# FPGA_PLLs.net
KiCad netlist of a schematic drawn in Altium Designer
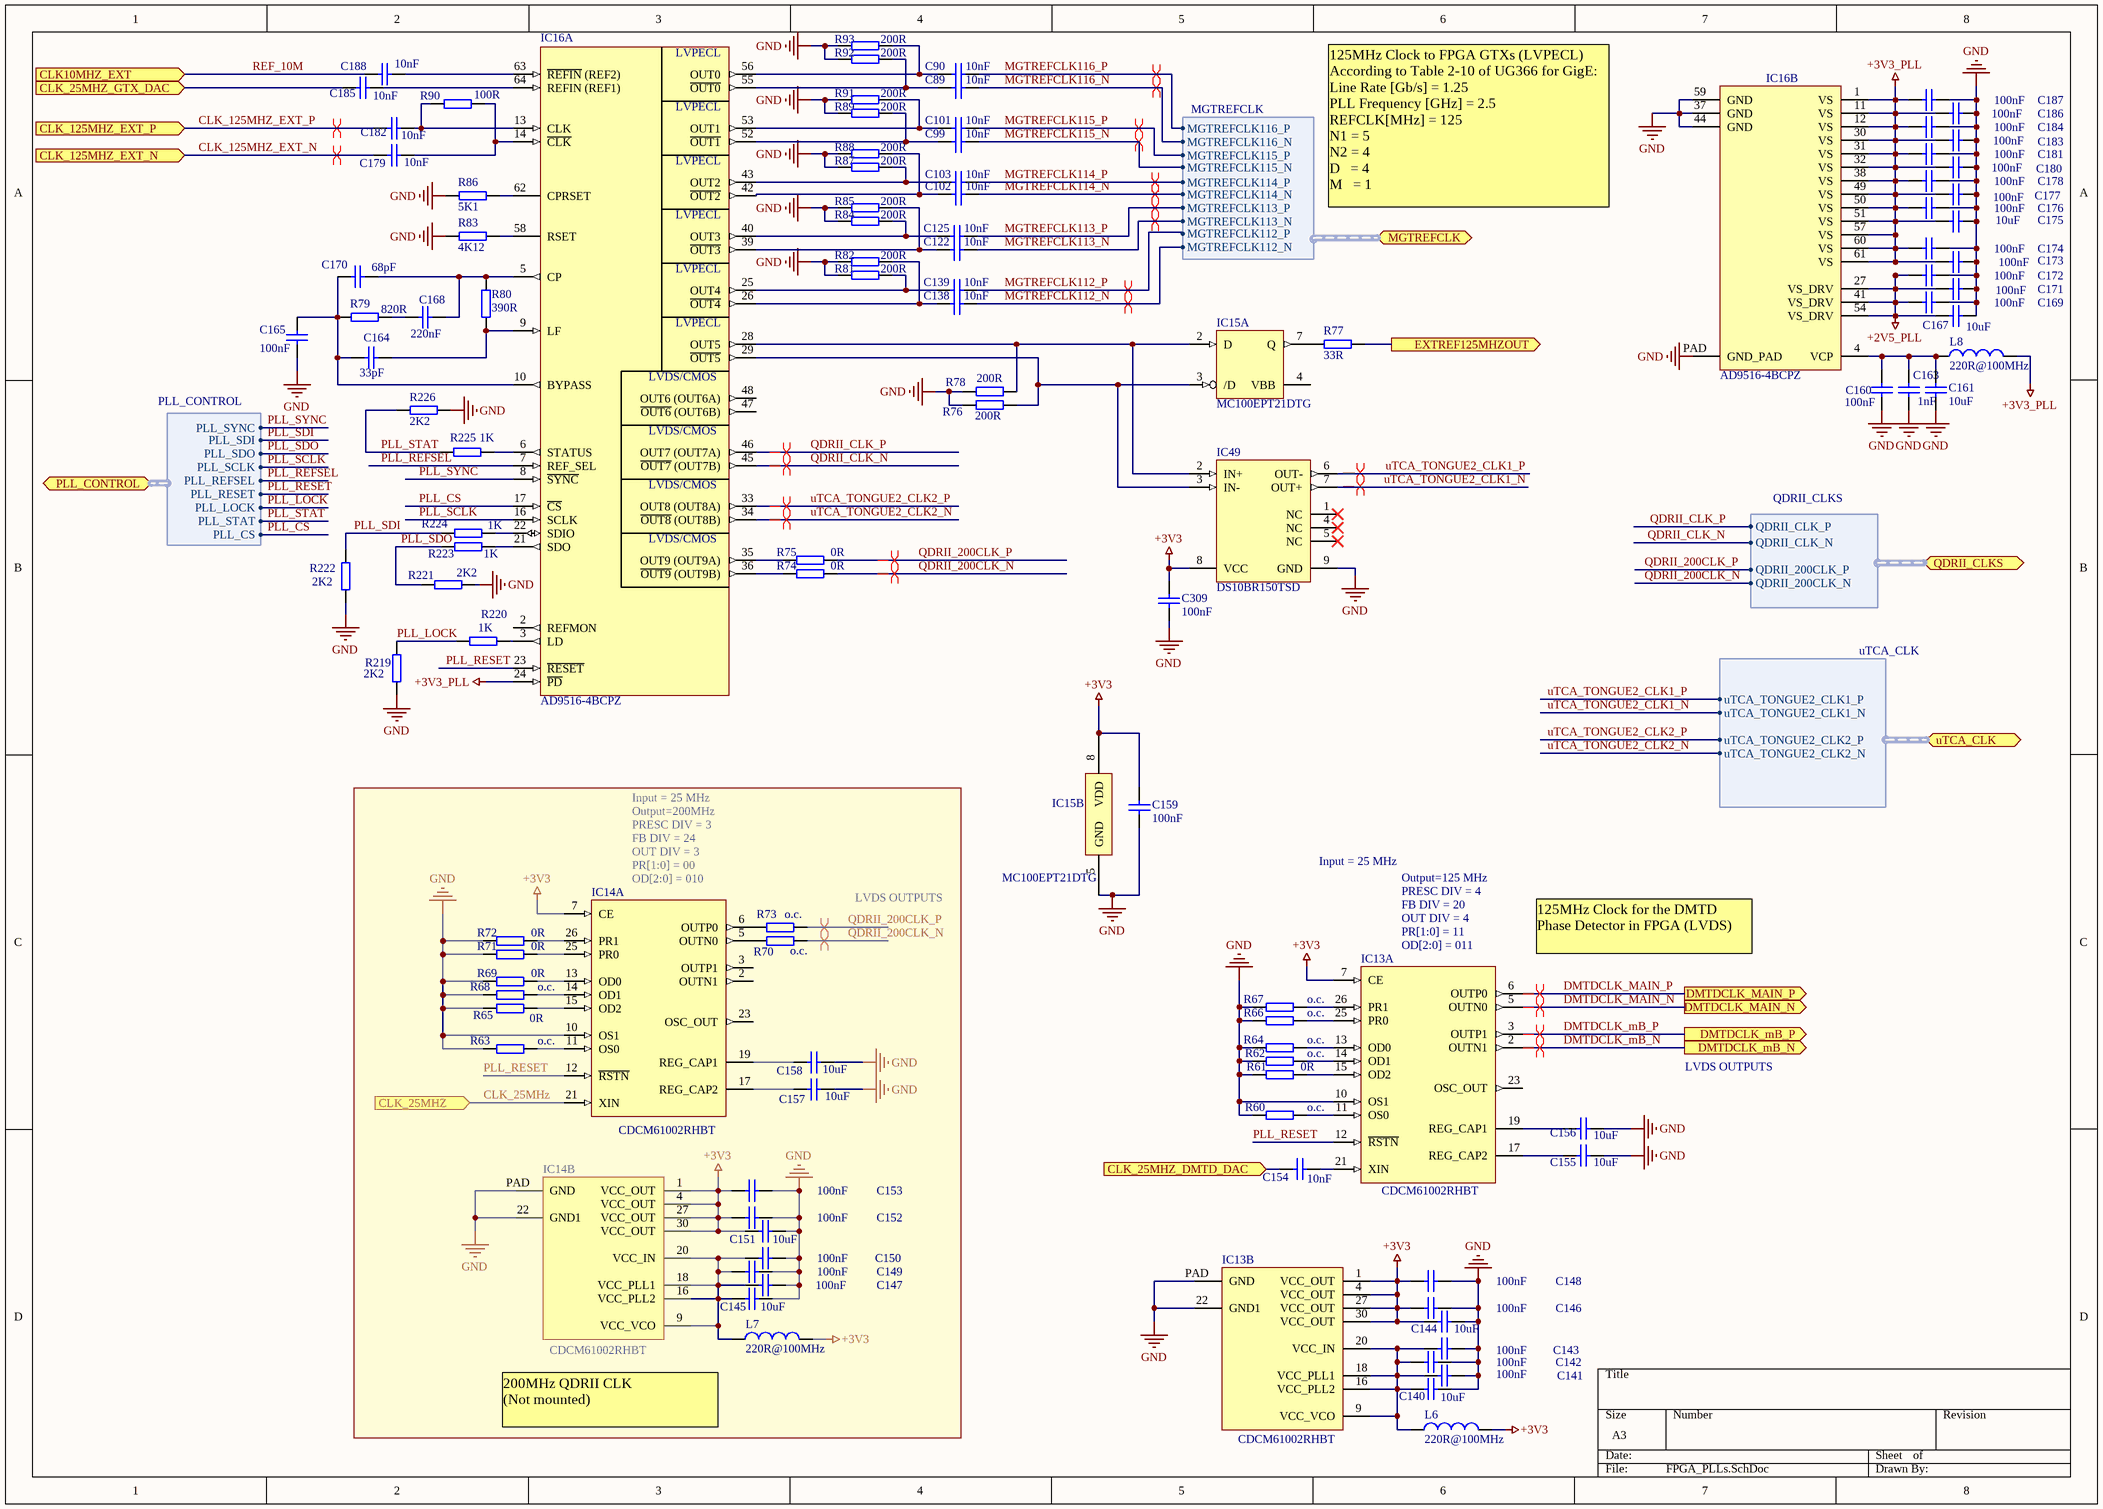
[diagram p0: FPGA_PLLs.SchDoc]

(export (version "E")
  (design (tool "Eeschema 10.0.6"))
  (components
    (comp (ref "C89")
      (value "10nF")
      (footprint "CC1005-0402")
      (description "Capacitor")
      (fields (field (name "TOLERANCE") "±10%") (field (name "VOLTAGE") "25V"))
      (libsource (lib "wr_switch") (part "Cap"))
    )
    (comp (ref "C90")
      (value "10nF")
      (footprint "CC1005-0402")
      (description "Capacitor")
      (fields (field (name "TOLERANCE") "±10%") (field (name "VOLTAGE") "25V"))
      (libsource (lib "wr_switch") (part "Cap"))
    )
    (comp (ref "C99")
      (value "10nF")
      (footprint "CC1005-0402")
      (description "Capacitor")
      (fields (field (name "TOLERANCE") "±10%") (field (name "VOLTAGE") "25V"))
      (libsource (lib "wr_switch") (part "Cap"))
    )
    (comp (ref "C101")
      (value "10nF")
      (footprint "CC1005-0402")
      (description "Capacitor")
      (fields (field (name "TOLERANCE") "±10%") (field (name "VOLTAGE") "25V"))
      (libsource (lib "wr_switch") (part "Cap"))
    )
    (comp (ref "C102")
      (value "10nF")
      (footprint "CC1005-0402")
      (description "Capacitor")
      (fields (field (name "TOLERANCE") "±10%") (field (name "VOLTAGE") "25V"))
      (libsource (lib "wr_switch") (part "Cap"))
    )
    (comp (ref "C103")
      (value "10nF")
      (footprint "CC1005-0402")
      (description "Capacitor")
      (fields (field (name "TOLERANCE") "±10%") (field (name "VOLTAGE") "25V"))
      (libsource (lib "wr_switch") (part "Cap"))
    )
    (comp (ref "C122")
      (value "10nF")
      (footprint "CC1005-0402")
      (description "Capacitor")
      (fields (field (name "TOLERANCE") "±10%") (field (name "VOLTAGE") "25V"))
      (libsource (lib "wr_switch") (part "Cap"))
    )
    (comp (ref "C125")
      (value "10nF")
      (footprint "CC1005-0402")
      (description "Capacitor")
      (fields (field (name "TOLERANCE") "±10%") (field (name "VOLTAGE") "25V"))
      (libsource (lib "wr_switch") (part "Cap"))
    )
    (comp (ref "C138")
      (value "10nF")
      (footprint "CC1005-0402")
      (description "Capacitor")
      (fields (field (name "TOLERANCE") "±10%") (field (name "VOLTAGE") "25V"))
      (libsource (lib "wr_switch") (part "Cap"))
    )
    (comp (ref "C139")
      (value "10nF")
      (footprint "CC1005-0402")
      (description "Capacitor")
      (fields (field (name "TOLERANCE") "±10%") (field (name "VOLTAGE") "25V"))
      (libsource (lib "wr_switch") (part "Cap"))
    )
    (comp (ref "C140")
      (value "10uF")
      (footprint "CC1608-0603")
      (description "Capacitor")
      (fields (field (name "TOLERANCE") "±20%") (field (name "VOLTAGE") "6.3V"))
      (libsource (lib "wr_switch") (part "Cap"))
    )
    (comp (ref "C141")
      (value "100nF")
      (footprint "CC1005-0402")
      (description "Capacitor")
      (fields (field (name "TOLERANCE") "±10%") (field (name "VOLTAGE") "16V"))
      (libsource (lib "wr_switch") (part "Cap"))
    )
    (comp (ref "C142")
      (value "100nF")
      (footprint "CC1005-0402")
      (description "Capacitor")
      (fields (field (name "TOLERANCE") "±10%") (field (name "VOLTAGE") "16V"))
      (libsource (lib "wr_switch") (part "Cap"))
    )
    (comp (ref "C143")
      (value "100nF")
      (footprint "CC1005-0402")
      (description "Capacitor")
      (fields (field (name "TOLERANCE") "±10%") (field (name "VOLTAGE") "16V"))
      (libsource (lib "wr_switch") (part "Cap"))
    )
    (comp (ref "C144")
      (value "10uF")
      (footprint "CC1608-0603")
      (description "Capacitor")
      (fields (field (name "TOLERANCE") "±20%") (field (name "VOLTAGE") "6.3V"))
      (libsource (lib "wr_switch") (part "Cap"))
    )
    (comp (ref "C145")
      (value "10uF")
      (footprint "CC1608-0603")
      (description "Capacitor")
      (fields (field (name "TOLERANCE") "±20%") (field (name "VOLTAGE") "6.3V"))
      (libsource (lib "wr_switch") (part "Cap"))
    )
    (comp (ref "C146")
      (value "100nF")
      (footprint "CC1005-0402")
      (description "Capacitor")
      (fields (field (name "TOLERANCE") "±10%") (field (name "VOLTAGE") "16V"))
      (libsource (lib "wr_switch") (part "Cap"))
    )
    (comp (ref "C147")
      (value "100nF")
      (footprint "CC1005-0402")
      (description "Capacitor")
      (fields (field (name "TOLERANCE") "±10%") (field (name "VOLTAGE") "16V"))
      (libsource (lib "wr_switch") (part "Cap"))
    )
    (comp (ref "C148")
      (value "100nF")
      (footprint "CC1005-0402")
      (description "Capacitor")
      (fields (field (name "TOLERANCE") "±10%") (field (name "VOLTAGE") "16V"))
      (libsource (lib "wr_switch") (part "Cap"))
    )
    (comp (ref "C149")
      (value "100nF")
      (footprint "CC1005-0402")
      (description "Capacitor")
      (fields (field (name "TOLERANCE") "±10%") (field (name "VOLTAGE") "16V"))
      (libsource (lib "wr_switch") (part "Cap"))
    )
    (comp (ref "C150")
      (value "100nF")
      (footprint "CC1005-0402")
      (description "Capacitor")
      (fields (field (name "TOLERANCE") "±10%") (field (name "VOLTAGE") "16V"))
      (libsource (lib "wr_switch") (part "Cap"))
    )
    (comp (ref "C151")
      (value "10uF")
      (footprint "CC1608-0603")
      (description "Capacitor")
      (fields (field (name "TOLERANCE") "±20%") (field (name "VOLTAGE") "6.3V"))
      (libsource (lib "wr_switch") (part "Cap"))
    )
    (comp (ref "C152")
      (value "100nF")
      (footprint "CC1005-0402")
      (description "Capacitor")
      (fields (field (name "TOLERANCE") "±10%") (field (name "VOLTAGE") "16V"))
      (libsource (lib "wr_switch") (part "Cap"))
    )
    (comp (ref "C153")
      (value "100nF")
      (footprint "CC1005-0402")
      (description "Capacitor")
      (fields (field (name "TOLERANCE") "±10%") (field (name "VOLTAGE") "16V"))
      (libsource (lib "wr_switch") (part "Cap"))
    )
    (comp (ref "C154")
      (value "10nF")
      (footprint "CC1005-0402")
      (description "Capacitor")
      (fields (field (name "TOLERANCE") "±10%") (field (name "VOLTAGE") "25V"))
      (libsource (lib "wr_switch") (part "Cap"))
    )
    (comp (ref "C155")
      (value "10uF")
      (footprint "CC1608-0603")
      (description "Capacitor")
      (fields (field (name "TOLERANCE") "±20%") (field (name "VOLTAGE") "6.3V"))
      (libsource (lib "wr_switch") (part "Cap"))
    )
    (comp (ref "C156")
      (value "10uF")
      (footprint "CC1608-0603")
      (description "Capacitor")
      (fields (field (name "TOLERANCE") "±20%") (field (name "VOLTAGE") "6.3V"))
      (libsource (lib "wr_switch") (part "Cap"))
    )
    (comp (ref "C157")
      (value "10uF")
      (footprint "CC1608-0603")
      (description "Capacitor")
      (fields (field (name "TOLERANCE") "±20%") (field (name "VOLTAGE") "6.3V"))
      (libsource (lib "wr_switch") (part "Cap"))
    )
    (comp (ref "C158")
      (value "10uF")
      (footprint "CC1608-0603")
      (description "Capacitor")
      (fields (field (name "TOLERANCE") "±20%") (field (name "VOLTAGE") "6.3V"))
      (libsource (lib "wr_switch") (part "Cap"))
    )
    (comp (ref "C159")
      (value "100nF")
      (footprint "CC1005-0402")
      (description "Capacitor")
      (fields (field (name "TOLERANCE") "±10%") (field (name "VOLTAGE") "16V"))
      (libsource (lib "wr_switch") (part "Cap"))
    )
    (comp (ref "C160")
      (value "100nF")
      (footprint "CC1005-0402")
      (description "Capacitor")
      (fields (field (name "TOLERANCE") "±10%") (field (name "VOLTAGE") "16V"))
      (libsource (lib "wr_switch") (part "Cap"))
    )
    (comp (ref "C161")
      (value "10uF")
      (footprint "CC1608-0603")
      (description "Capacitor")
      (fields (field (name "TOLERANCE") "±20%") (field (name "VOLTAGE") "6.3V"))
      (libsource (lib "wr_switch") (part "Cap"))
    )
    (comp (ref "C163")
      (value "1nF")
      (footprint "CC1005-0402")
      (description "Capacitor")
      (fields (field (name "TOLERANCE") "±10%") (field (name "VOLTAGE") "25V"))
      (libsource (lib "wr_switch") (part "Cap"))
    )
    (comp (ref "C164")
      (value "33pF")
      (footprint "CC1005-0402")
      (description "Capacitor")
      (fields (field (name "TOLERANCE") "±5%") (field (name "VOLTAGE") "50V"))
      (libsource (lib "wr_switch") (part "Cap"))
    )
    (comp (ref "C165")
      (value "100nF")
      (footprint "CC1005-0402")
      (description "Capacitor")
      (fields (field (name "TOLERANCE") "±10%") (field (name "VOLTAGE") "16V"))
      (libsource (lib "wr_switch") (part "Cap"))
    )
    (comp (ref "C167")
      (value "10uF")
      (footprint "CC1608-0603")
      (description "Capacitor")
      (fields (field (name "TOLERANCE") "±20%") (field (name "VOLTAGE") "6.3V"))
      (libsource (lib "wr_switch") (part "Cap"))
    )
    (comp (ref "C168")
      (value "220nF")
      (footprint "CC1005-0402")
      (description "Capacitor")
      (fields (field (name "TOLERANCE") "±10%") (field (name "VOLTAGE") "16V"))
      (libsource (lib "wr_switch") (part "Cap"))
    )
    (comp (ref "C169")
      (value "100nF")
      (footprint "CC1005-0402")
      (description "Capacitor")
      (fields (field (name "TOLERANCE") "±10%") (field (name "VOLTAGE") "16V"))
      (libsource (lib "wr_switch") (part "Cap"))
    )
    (comp (ref "C170")
      (value "68pF")
      (footprint "CC1005-0402")
      (description "Capacitor")
      (fields (field (name "TOLERANCE") "±5%") (field (name "VOLTAGE") "50V"))
      (libsource (lib "wr_switch") (part "Cap"))
    )
    (comp (ref "C171")
      (value "100nF")
      (footprint "CC1005-0402")
      (description "Capacitor")
      (fields (field (name "TOLERANCE") "±10%") (field (name "VOLTAGE") "16V"))
      (libsource (lib "wr_switch") (part "Cap"))
    )
    (comp (ref "C172")
      (value "100nF")
      (footprint "CC1005-0402")
      (description "Capacitor")
      (fields (field (name "TOLERANCE") "±10%") (field (name "VOLTAGE") "16V"))
      (libsource (lib "wr_switch") (part "Cap"))
    )
    (comp (ref "C173")
      (value "100nF")
      (footprint "CC1005-0402")
      (description "Capacitor")
      (fields (field (name "TOLERANCE") "±10%") (field (name "VOLTAGE") "16V"))
      (libsource (lib "wr_switch") (part "Cap"))
    )
    (comp (ref "C174")
      (value "100nF")
      (footprint "CC1005-0402")
      (description "Capacitor")
      (fields (field (name "TOLERANCE") "±10%") (field (name "VOLTAGE") "16V"))
      (libsource (lib "wr_switch") (part "Cap"))
    )
    (comp (ref "C175")
      (value "10uF")
      (footprint "CC1608-0603")
      (description "Capacitor")
      (fields (field (name "TOLERANCE") "±20%") (field (name "VOLTAGE") "6.3V"))
      (libsource (lib "wr_switch") (part "Cap"))
    )
    (comp (ref "C176")
      (value "100nF")
      (footprint "CC1005-0402")
      (description "Capacitor")
      (fields (field (name "TOLERANCE") "±10%") (field (name "VOLTAGE") "16V"))
      (libsource (lib "wr_switch") (part "Cap"))
    )
    (comp (ref "C177")
      (value "100nF")
      (footprint "CC1005-0402")
      (description "Capacitor")
      (fields (field (name "TOLERANCE") "±10%") (field (name "VOLTAGE") "16V"))
      (libsource (lib "wr_switch") (part "Cap"))
    )
    (comp (ref "C178")
      (value "100nF")
      (footprint "CC1005-0402")
      (description "Capacitor")
      (fields (field (name "TOLERANCE") "±10%") (field (name "VOLTAGE") "16V"))
      (libsource (lib "wr_switch") (part "Cap"))
    )
    (comp (ref "C179")
      (value "10nF")
      (footprint "CC1005-0402")
      (description "Capacitor")
      (fields (field (name "TOLERANCE") "±10%") (field (name "VOLTAGE") "25V"))
      (libsource (lib "wr_switch") (part "Cap"))
    )
    (comp (ref "C180")
      (value "100nF")
      (footprint "CC1005-0402")
      (description "Capacitor")
      (fields (field (name "TOLERANCE") "±10%") (field (name "VOLTAGE") "16V"))
      (libsource (lib "wr_switch") (part "Cap"))
    )
    (comp (ref "C181")
      (value "100nF")
      (footprint "CC1005-0402")
      (description "Capacitor")
      (fields (field (name "TOLERANCE") "±10%") (field (name "VOLTAGE") "16V"))
      (libsource (lib "wr_switch") (part "Cap"))
    )
    (comp (ref "C182")
      (value "10nF")
      (footprint "CC1005-0402")
      (description "Capacitor")
      (fields (field (name "TOLERANCE") "±10%") (field (name "VOLTAGE") "25V"))
      (libsource (lib "wr_switch") (part "Cap"))
    )
    (comp (ref "C183")
      (value "100nF")
      (footprint "CC1005-0402")
      (description "Capacitor")
      (fields (field (name "TOLERANCE") "±10%") (field (name "VOLTAGE") "16V"))
      (libsource (lib "wr_switch") (part "Cap"))
    )
    (comp (ref "C184")
      (value "100nF")
      (footprint "CC1005-0402")
      (description "Capacitor")
      (fields (field (name "TOLERANCE") "±10%") (field (name "VOLTAGE") "16V"))
      (libsource (lib "wr_switch") (part "Cap"))
    )
    (comp (ref "C185")
      (value "10nF")
      (footprint "CC1005-0402")
      (description "Capacitor")
      (fields (field (name "TOLERANCE") "±10%") (field (name "VOLTAGE") "25V"))
      (libsource (lib "wr_switch") (part "Cap"))
    )
    (comp (ref "C186")
      (value "100nF")
      (footprint "CC1005-0402")
      (description "Capacitor")
      (fields (field (name "TOLERANCE") "±10%") (field (name "VOLTAGE") "16V"))
      (libsource (lib "wr_switch") (part "Cap"))
    )
    (comp (ref "C187")
      (value "100nF")
      (footprint "CC1005-0402")
      (description "Capacitor")
      (fields (field (name "TOLERANCE") "±10%") (field (name "VOLTAGE") "16V"))
      (libsource (lib "wr_switch") (part "Cap"))
    )
    (comp (ref "C188")
      (value "10nF")
      (footprint "CC1005-0402")
      (description "Capacitor")
      (fields (field (name "TOLERANCE") "±10%") (field (name "VOLTAGE") "25V"))
      (libsource (lib "wr_switch") (part "Cap"))
    )
    (comp (ref "C309")
      (value "100nF")
      (footprint "CC1005-0402")
      (description "Capacitor")
      (fields (field (name "TOLERANCE") "±10%") (field (name "VOLTAGE") "16V"))
      (libsource (lib "wr_switch") (part "Cap"))
    )
    (comp (ref "IC13")
      (value "CDCM61002RHBT")
      (footprint "QFN32_POWERPAD")
      (description "Low Jitter Clock Generator, Two Outpust, Integrated VCO")
      (fields (field (name "MANUFACTURER") "Texas Instruments"))
      (libsource (lib "wr_switch") (part "CDCM61002"))
    )
    (comp (ref "IC14")
      (value "CDCM61002RHBT")
      (footprint "QFN32_POWERPAD")
      (description "Low Jitter Clock Generator, Two Outpust, Integrated VCO")
      (fields (field (name "MANUFACTURER") "Texas Instruments"))
      (libsource (lib "wr_switch") (part "CDCM61002"))
    )
    (comp (ref "IC15")
      (value "MC100EPT21DTG")
      (footprint "TSOP65P490-8AN")
      (description "ONSemi LVDS/LVPECL -> LVTTL/LVCMOS buffer")
      (libsource (lib "wr_switch") (part "MC100EPT21"))
    )
    (comp (ref "IC16")
      (value "AD9516-4BCPZ")
      (footprint "QFN50P900X900X100-64M")
      (description "PLL with clock fanout")
      (libsource (lib "wr_switch") (part "AD9516"))
    )
    (comp (ref "IC49")
      (value "DS10BR150TSD")
      (footprint "SDA08A")
      (description "1.0 Gbps LVDS Buffer/Repeater")
      (fields
        (field (name "MANUFACTURER") "National Semiconductor")
        (field (name "DIGIKEYPARTNUMBER") "DS10BR150TSDTR-ND")
      )
      (libsource (lib "NSC Interface") (part "DS10BR150TSD"))
    )
    (comp (ref "L6")
      (value "220R@100MHz Ferrite Bead")
      (footprint "0603")
      (description "ferrite bead")
      (fields (field (name "IMPEDANCE") "220R@100MHz"))
      (libsource (lib "wr_switch") (part "L_FERRITE_BEAD"))
    )
    (comp (ref "L7")
      (value "220R@100MHz Ferrite Bead")
      (footprint "0603")
      (description "ferrite bead")
      (fields (field (name "IMPEDANCE") "220R@100MHz"))
      (libsource (lib "wr_switch") (part "L_FERRITE_BEAD"))
    )
    (comp (ref "L8")
      (value "220R@100MHz Ferrite Bead")
      (footprint "0603")
      (description "ferrite bead")
      (fields (field (name "IMPEDANCE") "220R@100MHz"))
      (libsource (lib "wr_switch") (part "L_FERRITE_BEAD"))
    )
    (comp (ref "R60")
      (value "o.c.")
      (footprint "0402")
      (description "SMD Resistor")
      (libsource (lib "wr_switch") (part "RES_SMD"))
    )
    (comp (ref "R61")
      (value "0R")
      (footprint "0402")
      (description "SMD Resistor")
      (fields (field (name "TOLERANCE") "Jumper"))
      (libsource (lib "wr_switch") (part "RES_SMD"))
    )
    (comp (ref "R62")
      (value "o.c.")
      (footprint "0402")
      (description "SMD Resistor")
      (libsource (lib "wr_switch") (part "RES_SMD"))
    )
    (comp (ref "R63")
      (value "o.c.")
      (footprint "0402")
      (description "SMD Resistor")
      (libsource (lib "wr_switch") (part "RES_SMD"))
    )
    (comp (ref "R64")
      (value "o.c.")
      (footprint "0402")
      (description "SMD Resistor")
      (libsource (lib "wr_switch") (part "RES_SMD"))
    )
    (comp (ref "R65")
      (value "0R")
      (footprint "0402")
      (description "SMD Resistor")
      (fields (field (name "TOLERANCE") "Jumper"))
      (libsource (lib "wr_switch") (part "RES_SMD"))
    )
    (comp (ref "R66")
      (value "o.c.")
      (footprint "0402")
      (description "SMD Resistor")
      (libsource (lib "wr_switch") (part "RES_SMD"))
    )
    (comp (ref "R67")
      (value "o.c.")
      (footprint "0402")
      (description "SMD Resistor")
      (libsource (lib "wr_switch") (part "RES_SMD"))
    )
    (comp (ref "R68")
      (value "o.c.")
      (footprint "0402")
      (description "SMD Resistor")
      (libsource (lib "wr_switch") (part "RES_SMD"))
    )
    (comp (ref "R69")
      (value "0R")
      (footprint "0402")
      (description "SMD Resistor")
      (fields (field (name "TOLERANCE") "Jumper"))
      (libsource (lib "wr_switch") (part "RES_SMD"))
    )
    (comp (ref "R70")
      (value "o.c.")
      (footprint "0402")
      (description "SMD Resistor")
      (libsource (lib "wr_switch") (part "RES_SMD"))
    )
    (comp (ref "R71")
      (value "0R")
      (footprint "0402")
      (description "SMD Resistor")
      (fields (field (name "TOLERANCE") "Jumper"))
      (libsource (lib "wr_switch") (part "RES_SMD"))
    )
    (comp (ref "R72")
      (value "0R")
      (footprint "0402")
      (description "SMD Resistor")
      (fields (field (name "TOLERANCE") "Jumper"))
      (libsource (lib "wr_switch") (part "RES_SMD"))
    )
    (comp (ref "R73")
      (value "o.c.")
      (footprint "0402")
      (description "SMD Resistor")
      (libsource (lib "wr_switch") (part "RES_SMD"))
    )
    (comp (ref "R74")
      (value "0R")
      (footprint "0402")
      (description "SMD Resistor")
      (fields (field (name "TOLERANCE") "Jumper"))
      (libsource (lib "wr_switch") (part "RES_SMD"))
    )
    (comp (ref "R75")
      (value "0R")
      (footprint "0402")
      (description "SMD Resistor")
      (fields (field (name "TOLERANCE") "Jumper"))
      (libsource (lib "wr_switch") (part "RES_SMD"))
    )
    (comp (ref "R76")
      (value "200R")
      (footprint "0402")
      (description "SMD Resistor")
      (fields (field (name "TOLERANCE") "±1%"))
      (libsource (lib "wr_switch") (part "RES_SMD"))
    )
    (comp (ref "R77")
      (value "33R")
      (footprint "0603")
      (description "SMD Resistor")
      (fields (field (name "TOLERANCE") "±1%"))
      (libsource (lib "wr_switch") (part "RES_SMD"))
    )
    (comp (ref "R78")
      (value "200R")
      (footprint "0402")
      (description "SMD Resistor")
      (fields (field (name "TOLERANCE") "±1%"))
      (libsource (lib "wr_switch") (part "RES_SMD"))
    )
    (comp (ref "R79")
      (value "820R")
      (footprint "0402")
      (description "SMD Resistor")
      (fields (field (name "TOLERANCE") "±1%"))
      (libsource (lib "wr_switch") (part "RES_SMD"))
    )
    (comp (ref "R80")
      (value "390R")
      (footprint "0402")
      (description "SMD Resistor")
      (fields (field (name "TOLERANCE") "±1%"))
      (libsource (lib "wr_switch") (part "RES_SMD"))
    )
    (comp (ref "R81")
      (value "200R")
      (footprint "0402")
      (description "SMD Resistor")
      (fields (field (name "TOLERANCE") "±1%"))
      (libsource (lib "wr_switch") (part "RES_SMD"))
    )
    (comp (ref "R82")
      (value "200R")
      (footprint "0402")
      (description "SMD Resistor")
      (fields (field (name "TOLERANCE") "±1%"))
      (libsource (lib "wr_switch") (part "RES_SMD"))
    )
    (comp (ref "R83")
      (value "4K12")
      (footprint "0402")
      (description "SMD Resistor")
      (fields (field (name "TOLERANCE") "±1%"))
      (libsource (lib "wr_switch") (part "RES_SMD"))
    )
    (comp (ref "R84")
      (value "200R")
      (footprint "0402")
      (description "SMD Resistor")
      (fields (field (name "TOLERANCE") "±1%"))
      (libsource (lib "wr_switch") (part "RES_SMD"))
    )
    (comp (ref "R85")
      (value "200R")
      (footprint "0402")
      (description "SMD Resistor")
      (fields (field (name "TOLERANCE") "±1%"))
      (libsource (lib "wr_switch") (part "RES_SMD"))
    )
    (comp (ref "R86")
      (value "5K1")
      (footprint "0402")
      (description "SMD Resistor")
      (fields (field (name "TOLERANCE") "±1%"))
      (libsource (lib "wr_switch") (part "RES_SMD"))
    )
    (comp (ref "R87")
      (value "200R")
      (footprint "0402")
      (description "SMD Resistor")
      (fields (field (name "TOLERANCE") "±1%"))
      (libsource (lib "wr_switch") (part "RES_SMD"))
    )
    (comp (ref "R88")
      (value "200R")
      (footprint "0402")
      (description "SMD Resistor")
      (fields (field (name "TOLERANCE") "±1%"))
      (libsource (lib "wr_switch") (part "RES_SMD"))
    )
    (comp (ref "R89")
      (value "200R")
      (footprint "0402")
      (description "SMD Resistor")
      (fields (field (name "TOLERANCE") "±1%"))
      (libsource (lib "wr_switch") (part "RES_SMD"))
    )
    (comp (ref "R90")
      (value "100R")
      (footprint "0402")
      (description "SMD Resistor")
      (fields (field (name "TOLERANCE") "±1%"))
      (libsource (lib "wr_switch") (part "RES_SMD"))
    )
    (comp (ref "R91")
      (value "200R")
      (footprint "0402")
      (description "SMD Resistor")
      (fields (field (name "TOLERANCE") "±1%"))
      (libsource (lib "wr_switch") (part "RES_SMD"))
    )
    (comp (ref "R92")
      (value "200R")
      (footprint "0402")
      (description "SMD Resistor")
      (fields (field (name "TOLERANCE") "±1%"))
      (libsource (lib "wr_switch") (part "RES_SMD"))
    )
    (comp (ref "R93")
      (value "200R")
      (footprint "0402")
      (description "SMD Resistor")
      (fields (field (name "TOLERANCE") "±1%"))
      (libsource (lib "wr_switch") (part "RES_SMD"))
    )
    (comp (ref "R219")
      (value "2K2")
      (footprint "0402")
      (description "SMD Resistor")
      (fields (field (name "TOLERANCE") "±1%"))
      (libsource (lib "wr_switch") (part "RES_SMD"))
    )
    (comp (ref "R220")
      (value "1K")
      (footprint "0402")
      (description "SMD Resistor")
      (fields (field (name "TOLERANCE") "±1%"))
      (libsource (lib "wr_switch") (part "RES_SMD"))
    )
    (comp (ref "R221")
      (value "2K2")
      (footprint "0402")
      (description "SMD Resistor")
      (fields (field (name "TOLERANCE") "±1%"))
      (libsource (lib "wr_switch") (part "RES_SMD"))
    )
    (comp (ref "R222")
      (value "2K2")
      (footprint "0402")
      (description "SMD Resistor")
      (fields (field (name "TOLERANCE") "±1%"))
      (libsource (lib "wr_switch") (part "RES_SMD"))
    )
    (comp (ref "R223")
      (value "1K")
      (footprint "0402")
      (description "SMD Resistor")
      (fields (field (name "TOLERANCE") "±1%"))
      (libsource (lib "wr_switch") (part "RES_SMD"))
    )
    (comp (ref "R224")
      (value "1K")
      (footprint "0402")
      (description "SMD Resistor")
      (fields (field (name "TOLERANCE") "±1%"))
      (libsource (lib "wr_switch") (part "RES_SMD"))
    )
    (comp (ref "R225")
      (value "1K")
      (footprint "0402")
      (description "SMD Resistor")
      (fields (field (name "TOLERANCE") "±1%"))
      (libsource (lib "wr_switch") (part "RES_SMD"))
    )
    (comp (ref "R226")
      (value "2K2")
      (footprint "0402")
      (description "SMD Resistor")
      (fields (field (name "TOLERANCE") "±1%"))
      (libsource (lib "wr_switch") (part "RES_SMD"))
    )
  )
  (nets
    (net (code "5") (name "+2V5_PLL") (class "Default")
      (node (ref "C167") (pin "1") (pinfunction "1_1") (pintype "passive"))
      (node (ref "C169") (pin "2") (pinfunction "2_2") (pintype "passive"))
      (node (ref "C171") (pin "2") (pinfunction "2_2") (pintype "passive"))
      (node (ref "C172") (pin "2") (pinfunction "2_2") (pintype "passive"))
      (node (ref "IC16") (pin "27") (pinfunction "VS_DRV_27") (pintype "power_in"))
      (node (ref "IC16") (pin "41") (pinfunction "VS_DRV_41") (pintype "power_in"))
      (node (ref "IC16") (pin "54") (pinfunction "VS_DRV_54") (pintype "power_in"))
    )
    (net (code "6") (name "+3V3") (class "Default")
      (node (ref "C144") (pin "1") (pinfunction "1_1") (pintype "passive"))
      (node (ref "C146") (pin "2") (pinfunction "2_2") (pintype "passive"))
      (node (ref "C148") (pin "2") (pinfunction "2_2") (pintype "passive"))
      (node (ref "C151") (pin "1") (pinfunction "1_1") (pintype "passive"))
      (node (ref "C152") (pin "2") (pinfunction "2_2") (pintype "passive"))
      (node (ref "C153") (pin "2") (pinfunction "2_2") (pintype "passive"))
      (node (ref "C159") (pin "1") (pinfunction "1_1") (pintype "passive"))
      (node (ref "C309") (pin "1") (pinfunction "1_1") (pintype "passive"))
      (node (ref "IC13") (pin "1") (pinfunction "VCC_OUT_1") (pintype "power_in"))
      (node (ref "IC13") (pin "27") (pinfunction "VCC_OUT_27") (pintype "power_in"))
      (node (ref "IC13") (pin "30") (pinfunction "VCC_OUT_30") (pintype "power_in"))
      (node (ref "IC13") (pin "4") (pinfunction "VCC_OUT_4") (pintype "power_in"))
      (node (ref "IC13") (pin "7") (pinfunction "CE_7") (pintype "input"))
      (node (ref "IC14") (pin "1") (pinfunction "VCC_OUT_1") (pintype "power_in"))
      (node (ref "IC14") (pin "27") (pinfunction "VCC_OUT_27") (pintype "power_in"))
      (node (ref "IC14") (pin "30") (pinfunction "VCC_OUT_30") (pintype "power_in"))
      (node (ref "IC14") (pin "4") (pinfunction "VCC_OUT_4") (pintype "power_in"))
      (node (ref "IC14") (pin "7") (pinfunction "CE_7") (pintype "input"))
      (node (ref "IC15") (pin "8") (pinfunction "VDD_8") (pintype "passive"))
      (node (ref "IC49") (pin "8") (pinfunction "VCC_8") (pintype "power_in"))
      (node (ref "L6") (pin "2") (pinfunction "2_2") (pintype "passive"))
      (node (ref "L7") (pin "2") (pinfunction "2_2") (pintype "passive"))
    )
    (net (code "7") (name "+3V3_PLL") (class "Default")
      (node (ref "C173") (pin "2") (pinfunction "2_2") (pintype "passive"))
      (node (ref "C174") (pin "2") (pinfunction "2_2") (pintype "passive"))
      (node (ref "C175") (pin "1") (pinfunction "1_1") (pintype "passive"))
      (node (ref "C176") (pin "2") (pinfunction "2_2") (pintype "passive"))
      (node (ref "C177") (pin "2") (pinfunction "2_2") (pintype "passive"))
      (node (ref "C178") (pin "2") (pinfunction "2_2") (pintype "passive"))
      (node (ref "C180") (pin "2") (pinfunction "2_2") (pintype "passive"))
      (node (ref "C181") (pin "2") (pinfunction "2_2") (pintype "passive"))
      (node (ref "C183") (pin "2") (pinfunction "2_2") (pintype "passive"))
      (node (ref "C184") (pin "2") (pinfunction "2_2") (pintype "passive"))
      (node (ref "C186") (pin "2") (pinfunction "2_2") (pintype "passive"))
      (node (ref "C187") (pin "2") (pinfunction "2_2") (pintype "passive"))
      (node (ref "IC16") (pin "1") (pinfunction "VS_1") (pintype "power_in"))
      (node (ref "IC16") (pin "11") (pinfunction "VS_11") (pintype "power_in"))
      (node (ref "IC16") (pin "12") (pinfunction "VS_12") (pintype "power_in"))
      (node (ref "IC16") (pin "24") (pinfunction "~{PD}_24") (pintype "input"))
      (node (ref "IC16") (pin "30") (pinfunction "VS_30") (pintype "power_in"))
      (node (ref "IC16") (pin "31") (pinfunction "VS_31") (pintype "power_in"))
      (node (ref "IC16") (pin "32") (pinfunction "VS_32") (pintype "power_in"))
      (node (ref "IC16") (pin "38") (pinfunction "VS_38") (pintype "power_in"))
      (node (ref "IC16") (pin "49") (pinfunction "VS_49") (pintype "power_in"))
      (node (ref "IC16") (pin "50") (pinfunction "VS_50") (pintype "power_in"))
      (node (ref "IC16") (pin "51") (pinfunction "VS_51") (pintype "power_in"))
      (node (ref "IC16") (pin "57") (pinfunction "VS_57") (pintype "power_in"))
      (node (ref "IC16") (pin "60") (pinfunction "VS_60") (pintype "power_in"))
      (node (ref "IC16") (pin "61") (pinfunction "VS_61") (pintype "power_in"))
      (node (ref "L8") (pin "2") (pinfunction "2_2") (pintype "passive"))
    )
    (net (code "8") (name "/CLK_25MHZ_DMTD_DAC") (class "Default")
      (node (ref "C154") (pin "2") (pinfunction "2_2") (pintype "passive"))
    )
    (net (code "9") (name "/CLK_25MHZ_GTX_DAC") (class "Default")
      (node (ref "C185") (pin "1") (pinfunction "1_1") (pintype "passive"))
    )
    (net (code "10") (name "/CLK_25MHz") (class "Default")
      (node (ref "IC14") (pin "21") (pinfunction "XIN_21") (pintype "input"))
    )
    (net (code "11") (name "/CLK_125MHZ_EXT_N") (class "Default")
      (node (ref "C179") (pin "1") (pinfunction "1_1") (pintype "passive"))
    )
    (net (code "12") (name "/CLK_125MHZ_EXT_P") (class "Default")
      (node (ref "C182") (pin "1") (pinfunction "1_1") (pintype "passive"))
    )
    (net (code "13") (name "/DMTDCLK_MAIN_N") (class "Default")
      (node (ref "IC13") (pin "5") (pinfunction "OUTN0_5") (pintype "output"))
    )
    (net (code "14") (name "/DMTDCLK_MAIN_P") (class "Default")
      (node (ref "IC13") (pin "6") (pinfunction "OUTP0_6") (pintype "output"))
    )
    (net (code "15") (name "/DMTDCLK_mB_N") (class "Default")
      (node (ref "IC13") (pin "2") (pinfunction "OUTN1_2") (pintype "output"))
    )
    (net (code "16") (name "/DMTDCLK_mB_P") (class "Default")
      (node (ref "IC13") (pin "3") (pinfunction "OUTP1_3") (pintype "output"))
    )
    (net (code "17") (name "/EXTREF125MHZOUT") (class "Default")
      (node (ref "R77") (pin "2") (pinfunction "2_2") (pintype "passive"))
    )
    (net (code "18") (name "/MGTREFCLK112_N") (class "Default")
      (node (ref "C138") (pin "1") (pinfunction "1_1") (pintype "passive"))
    )
    (net (code "19") (name "/MGTREFCLK112_P") (class "Default")
      (node (ref "C139") (pin "1") (pinfunction "1_1") (pintype "passive"))
    )
    (net (code "20") (name "/MGTREFCLK113_N") (class "Default")
      (node (ref "C122") (pin "1") (pinfunction "1_1") (pintype "passive"))
    )
    (net (code "21") (name "/MGTREFCLK113_P") (class "Default")
      (node (ref "C125") (pin "1") (pinfunction "1_1") (pintype "passive"))
    )
    (net (code "22") (name "/MGTREFCLK114_N") (class "Default")
      (node (ref "C102") (pin "1") (pinfunction "1_1") (pintype "passive"))
    )
    (net (code "23") (name "/MGTREFCLK114_P") (class "Default")
      (node (ref "C103") (pin "1") (pinfunction "1_1") (pintype "passive"))
    )
    (net (code "24") (name "/MGTREFCLK115_N") (class "Default")
      (node (ref "C99") (pin "1") (pinfunction "1_1") (pintype "passive"))
    )
    (net (code "25") (name "/MGTREFCLK115_P") (class "Default")
      (node (ref "C101") (pin "1") (pinfunction "1_1") (pintype "passive"))
    )
    (net (code "26") (name "/MGTREFCLK116_N") (class "Default")
      (node (ref "C89") (pin "1") (pinfunction "1_1") (pintype "passive"))
    )
    (net (code "27") (name "/MGTREFCLK116_P") (class "Default")
      (node (ref "C90") (pin "1") (pinfunction "1_1") (pintype "passive"))
    )
    (net (code "28") (name "/PLL_CS") (class "Default")
      (node (ref "IC16") (pin "17") (pinfunction "~{CS}_17") (pintype "input"))
    )
    (net (code "29") (name "/PLL_LOCK") (class "Default")
      (node (ref "R219") (pin "1") (pinfunction "1_1") (pintype "passive"))
      (node (ref "R220") (pin "2") (pinfunction "2_2") (pintype "passive"))
    )
    (net (code "30") (name "/PLL_REFSEL") (class "Default")
      (node (ref "IC16") (pin "7") (pinfunction "REF_SEL_7") (pintype "input"))
    )
    (net (code "31") (name "/PLL_RESET") (class "Default")
      (node (ref "IC13") (pin "12") (pinfunction "~{RSTN}_12") (pintype "input"))
      (node (ref "IC14") (pin "12") (pinfunction "~{RSTN}_12") (pintype "input"))
      (node (ref "IC16") (pin "23") (pinfunction "~{RESET}_23") (pintype "input"))
    )
    (net (code "32") (name "/PLL_SCLK") (class "Default")
      (node (ref "IC16") (pin "16") (pinfunction "SCLK_16") (pintype "input"))
    )
    (net (code "33") (name "/PLL_SDI") (class "Default")
      (node (ref "R222") (pin "1") (pinfunction "1_1") (pintype "passive"))
      (node (ref "R224") (pin "2") (pinfunction "2_2") (pintype "passive"))
    )
    (net (code "34") (name "/PLL_SDO") (class "Default")
      (node (ref "R221") (pin "1") (pinfunction "1_1") (pintype "passive"))
      (node (ref "R223") (pin "2") (pinfunction "2_2") (pintype "passive"))
    )
    (net (code "35") (name "/PLL_STAT") (class "Default")
      (node (ref "R225") (pin "2") (pinfunction "2_2") (pintype "passive"))
      (node (ref "R226") (pin "1") (pinfunction "1_1") (pintype "passive"))
    )
    (net (code "36") (name "/PLL_SYNC") (class "Default")
      (node (ref "IC16") (pin "8") (pinfunction "~{SYNC}_8") (pintype "input"))
    )
    (net (code "37") (name "/QDRII_200CLK_N") (class "Default")
      (node (ref "R70") (pin "1") (pinfunction "1_1") (pintype "passive"))
      (node (ref "R74") (pin "2") (pinfunction "2_2") (pintype "passive"))
    )
    (net (code "38") (name "/QDRII_200CLK_P") (class "Default")
      (node (ref "R73") (pin "1") (pinfunction "1_1") (pintype "passive"))
      (node (ref "R75") (pin "2") (pinfunction "2_2") (pintype "passive"))
    )
    (net (code "39") (name "/QDRII_CLK_N") (class "Default")
      (node (ref "IC16") (pin "45") (pinfunction "~{OUT7}_(OUT7B)_45") (pintype "output"))
    )
    (net (code "40") (name "/QDRII_CLK_P") (class "Default")
      (node (ref "IC16") (pin "46") (pinfunction "OUT7_(OUT7A)_46") (pintype "output"))
    )
    (net (code "41") (name "/REF_10M") (class "Default")
      (node (ref "C188") (pin "1") (pinfunction "1_1") (pintype "passive"))
    )
    (net (code "42") (name "/uTCA_TONGUE2_CLK1_N") (class "Default")
      (node (ref "IC49") (pin "7") (pinfunction "OUT+_7") (pintype "output"))
    )
    (net (code "43") (name "/uTCA_TONGUE2_CLK1_P") (class "Default")
      (node (ref "IC49") (pin "6") (pinfunction "OUT-_6") (pintype "output"))
    )
    (net (code "44") (name "/uTCA_TONGUE2_CLK2_N") (class "Default")
      (node (ref "IC16") (pin "34") (pinfunction "~{OUT8}_(OUT8B)_34") (pintype "output"))
    )
    (net (code "45") (name "/uTCA_TONGUE2_CLK2_P") (class "Default")
      (node (ref "IC16") (pin "33") (pinfunction "OUT8_(OUT8A)_33") (pintype "output"))
    )
    (net (code "50") (name "GND") (class "Default")
      (node (ref "C140") (pin "2") (pinfunction "2_2") (pintype "passive"))
      (node (ref "C141") (pin "1") (pinfunction "1_1") (pintype "passive"))
      (node (ref "C142") (pin "1") (pinfunction "1_1") (pintype "passive"))
      (node (ref "C143") (pin "1") (pinfunction "1_1") (pintype "passive"))
      (node (ref "C144") (pin "2") (pinfunction "2_2") (pintype "passive"))
      (node (ref "C145") (pin "2") (pinfunction "2_2") (pintype "passive"))
      (node (ref "C146") (pin "1") (pinfunction "1_1") (pintype "passive"))
      (node (ref "C147") (pin "1") (pinfunction "1_1") (pintype "passive"))
      (node (ref "C148") (pin "1") (pinfunction "1_1") (pintype "passive"))
      (node (ref "C149") (pin "1") (pinfunction "1_1") (pintype "passive"))
      (node (ref "C150") (pin "1") (pinfunction "1_1") (pintype "passive"))
      (node (ref "C151") (pin "2") (pinfunction "2_2") (pintype "passive"))
      (node (ref "C152") (pin "1") (pinfunction "1_1") (pintype "passive"))
      (node (ref "C153") (pin "1") (pinfunction "1_1") (pintype "passive"))
      (node (ref "C155") (pin "2") (pinfunction "2_2") (pintype "passive"))
      (node (ref "C156") (pin "2") (pinfunction "2_2") (pintype "passive"))
      (node (ref "C157") (pin "2") (pinfunction "2_2") (pintype "passive"))
      (node (ref "C158") (pin "2") (pinfunction "2_2") (pintype "passive"))
      (node (ref "C159") (pin "2") (pinfunction "2_2") (pintype "passive"))
      (node (ref "C160") (pin "2") (pinfunction "2_2") (pintype "passive"))
      (node (ref "C161") (pin "1") (pinfunction "1_1") (pintype "passive"))
      (node (ref "C163") (pin "1") (pinfunction "1_1") (pintype "passive"))
      (node (ref "C165") (pin "2") (pinfunction "2_2") (pintype "passive"))
      (node (ref "C167") (pin "2") (pinfunction "2_2") (pintype "passive"))
      (node (ref "C169") (pin "1") (pinfunction "1_1") (pintype "passive"))
      (node (ref "C171") (pin "1") (pinfunction "1_1") (pintype "passive"))
      (node (ref "C172") (pin "1") (pinfunction "1_1") (pintype "passive"))
      (node (ref "C173") (pin "1") (pinfunction "1_1") (pintype "passive"))
      (node (ref "C174") (pin "1") (pinfunction "1_1") (pintype "passive"))
      (node (ref "C175") (pin "2") (pinfunction "2_2") (pintype "passive"))
      (node (ref "C176") (pin "1") (pinfunction "1_1") (pintype "passive"))
      (node (ref "C177") (pin "1") (pinfunction "1_1") (pintype "passive"))
      (node (ref "C178") (pin "1") (pinfunction "1_1") (pintype "passive"))
      (node (ref "C180") (pin "1") (pinfunction "1_1") (pintype "passive"))
      (node (ref "C181") (pin "1") (pinfunction "1_1") (pintype "passive"))
      (node (ref "C183") (pin "1") (pinfunction "1_1") (pintype "passive"))
      (node (ref "C184") (pin "1") (pinfunction "1_1") (pintype "passive"))
      (node (ref "C186") (pin "1") (pinfunction "1_1") (pintype "passive"))
      (node (ref "C187") (pin "1") (pinfunction "1_1") (pintype "passive"))
      (node (ref "C309") (pin "2") (pinfunction "2_2") (pintype "passive"))
      (node (ref "IC13") (pin "10") (pinfunction "OS1_10") (pintype "input"))
      (node (ref "IC13") (pin "22") (pinfunction "GND1_22") (pintype "power_in"))
      (node (ref "IC13") (pin "PAD") (pinfunction "GND_PAD") (pintype "power_in"))
      (node (ref "IC14") (pin "10") (pinfunction "OS1_10") (pintype "input"))
      (node (ref "IC14") (pin "22") (pinfunction "GND1_22") (pintype "power_in"))
      (node (ref "IC14") (pin "PAD") (pinfunction "GND_PAD") (pintype "power_in"))
      (node (ref "IC15") (pin "5") (pinfunction "GND_5") (pintype "passive"))
      (node (ref "IC16") (pin "37") (pinfunction "GND_37") (pintype "power_in"))
      (node (ref "IC16") (pin "44") (pinfunction "GND_44") (pintype "power_in"))
      (node (ref "IC16") (pin "59") (pinfunction "GND_59") (pintype "power_in"))
      (node (ref "IC16") (pin "PAD") (pinfunction "GND_PAD_PAD") (pintype "power_in"))
      (node (ref "IC49") (pin "9") (pinfunction "GND_9") (pintype "power_in"))
      (node (ref "R219") (pin "2") (pinfunction "2_2") (pintype "passive"))
      (node (ref "R221") (pin "2") (pinfunction "2_2") (pintype "passive"))
      (node (ref "R222") (pin "2") (pinfunction "2_2") (pintype "passive"))
      (node (ref "R226") (pin "2") (pinfunction "2_2") (pintype "passive"))
      (node (ref "R60") (pin "2") (pinfunction "2_2") (pintype "passive"))
      (node (ref "R61") (pin "1") (pinfunction "1_1") (pintype "passive"))
      (node (ref "R62") (pin "2") (pinfunction "2_2") (pintype "passive"))
      (node (ref "R63") (pin "2") (pinfunction "2_2") (pintype "passive"))
      (node (ref "R64") (pin "2") (pinfunction "2_2") (pintype "passive"))
      (node (ref "R65") (pin "1") (pinfunction "1_1") (pintype "passive"))
      (node (ref "R66") (pin "2") (pinfunction "2_2") (pintype "passive"))
      (node (ref "R67") (pin "2") (pinfunction "2_2") (pintype "passive"))
      (node (ref "R68") (pin "2") (pinfunction "2_2") (pintype "passive"))
      (node (ref "R69") (pin "1") (pinfunction "1_1") (pintype "passive"))
      (node (ref "R71") (pin "1") (pinfunction "1_1") (pintype "passive"))
      (node (ref "R72") (pin "1") (pinfunction "1_1") (pintype "passive"))
      (node (ref "R76") (pin "2") (pinfunction "2_2") (pintype "passive"))
      (node (ref "R78") (pin "2") (pinfunction "2_2") (pintype "passive"))
      (node (ref "R81") (pin "2") (pinfunction "2_2") (pintype "passive"))
      (node (ref "R82") (pin "2") (pinfunction "2_2") (pintype "passive"))
      (node (ref "R83") (pin "1") (pinfunction "1_1") (pintype "passive"))
      (node (ref "R84") (pin "2") (pinfunction "2_2") (pintype "passive"))
      (node (ref "R85") (pin "2") (pinfunction "2_2") (pintype "passive"))
      (node (ref "R86") (pin "1") (pinfunction "1_1") (pintype "passive"))
      (node (ref "R87") (pin "2") (pinfunction "2_2") (pintype "passive"))
      (node (ref "R88") (pin "2") (pinfunction "2_2") (pintype "passive"))
      (node (ref "R89") (pin "2") (pinfunction "2_2") (pintype "passive"))
      (node (ref "R91") (pin "2") (pinfunction "2_2") (pintype "passive"))
      (node (ref "R92") (pin "2") (pinfunction "2_2") (pintype "passive"))
      (node (ref "R93") (pin "2") (pinfunction "2_2") (pintype "passive"))
    )
    (net (code "51") (name "Net-(C168-Pad1)") (class "Default")
      (node (ref "C168") (pin "1") (pinfunction "1_1") (pintype "passive"))
      (node (ref "R79") (pin "2") (pinfunction "2_2") (pintype "passive"))
    )
    (net (code "52") (name "Net-(IC13A-OD0)") (class "Default")
      (node (ref "IC13") (pin "13") (pinfunction "OD0_13") (pintype "input"))
      (node (ref "R64") (pin "1") (pinfunction "1_1") (pintype "passive"))
    )
    (net (code "53") (name "Net-(IC13A-OD1)") (class "Default")
      (node (ref "IC13") (pin "14") (pinfunction "OD1_14") (pintype "input"))
      (node (ref "R62") (pin "1") (pinfunction "1_1") (pintype "passive"))
    )
    (net (code "54") (name "Net-(IC13A-OD2)") (class "Default")
      (node (ref "IC13") (pin "15") (pinfunction "OD2_15") (pintype "input"))
      (node (ref "R61") (pin "2") (pinfunction "2_2") (pintype "passive"))
    )
    (net (code "55") (name "Net-(IC13A-OS0)") (class "Default")
      (node (ref "IC13") (pin "11") (pinfunction "OS0_11") (pintype "input"))
      (node (ref "R60") (pin "1") (pinfunction "1_1") (pintype "passive"))
    )
    (net (code "56") (name "Net-(IC13A-PR0)") (class "Default")
      (node (ref "IC13") (pin "25") (pinfunction "PR0_25") (pintype "input"))
      (node (ref "R66") (pin "1") (pinfunction "1_1") (pintype "passive"))
    )
    (net (code "57") (name "Net-(IC13A-PR1)") (class "Default")
      (node (ref "IC13") (pin "26") (pinfunction "PR1_26") (pintype "input"))
      (node (ref "R67") (pin "1") (pinfunction "1_1") (pintype "passive"))
    )
    (net (code "58") (name "Net-(IC13A-REG_CAP1)") (class "Default")
      (node (ref "C156") (pin "1") (pinfunction "1_1") (pintype "passive"))
      (node (ref "IC13") (pin "19") (pinfunction "REG_CAP1_19") (pintype "passive"))
    )
    (net (code "59") (name "Net-(IC13A-REG_CAP2)") (class "Default")
      (node (ref "C155") (pin "1") (pinfunction "1_1") (pintype "passive"))
      (node (ref "IC13") (pin "17") (pinfunction "REG_CAP2_17") (pintype "passive"))
    )
    (net (code "60") (name "Net-(IC13A-XIN)") (class "Default")
      (node (ref "C154") (pin "1") (pinfunction "1_1") (pintype "passive"))
      (node (ref "IC13") (pin "21") (pinfunction "XIN_21") (pintype "input"))
    )
    (net (code "61") (name "Net-(IC13B-VCC_IN)") (class "Default")
      (node (ref "C140") (pin "1") (pinfunction "1_1") (pintype "passive"))
      (node (ref "C141") (pin "2") (pinfunction "2_2") (pintype "passive"))
      (node (ref "C142") (pin "2") (pinfunction "2_2") (pintype "passive"))
      (node (ref "C143") (pin "2") (pinfunction "2_2") (pintype "passive"))
      (node (ref "IC13") (pin "16") (pinfunction "VCC_PLL2_16") (pintype "power_in"))
      (node (ref "IC13") (pin "18") (pinfunction "VCC_PLL1_18") (pintype "power_in"))
      (node (ref "IC13") (pin "20") (pinfunction "VCC_IN_20") (pintype "power_in"))
      (node (ref "IC13") (pin "9") (pinfunction "VCC_VCO_9") (pintype "power_in"))
      (node (ref "L6") (pin "1") (pinfunction "1_1") (pintype "passive"))
    )
    (net (code "62") (name "Net-(IC14A-OD0)") (class "Default")
      (node (ref "IC14") (pin "13") (pinfunction "OD0_13") (pintype "input"))
      (node (ref "R69") (pin "2") (pinfunction "2_2") (pintype "passive"))
    )
    (net (code "63") (name "Net-(IC14A-OD1)") (class "Default")
      (node (ref "IC14") (pin "14") (pinfunction "OD1_14") (pintype "input"))
      (node (ref "R68") (pin "1") (pinfunction "1_1") (pintype "passive"))
    )
    (net (code "64") (name "Net-(IC14A-OD2)") (class "Default")
      (node (ref "IC14") (pin "15") (pinfunction "OD2_15") (pintype "input"))
      (node (ref "R65") (pin "2") (pinfunction "2_2") (pintype "passive"))
    )
    (net (code "65") (name "Net-(IC14A-OS0)") (class "Default")
      (node (ref "IC14") (pin "11") (pinfunction "OS0_11") (pintype "input"))
      (node (ref "R63") (pin "1") (pinfunction "1_1") (pintype "passive"))
    )
    (net (code "66") (name "Net-(IC14A-OUTN0)") (class "Default")
      (node (ref "IC14") (pin "5") (pinfunction "OUTN0_5") (pintype "output"))
      (node (ref "R70") (pin "2") (pinfunction "2_2") (pintype "passive"))
    )
    (net (code "67") (name "Net-(IC14A-OUTP0)") (class "Default")
      (node (ref "IC14") (pin "6") (pinfunction "OUTP0_6") (pintype "output"))
      (node (ref "R73") (pin "2") (pinfunction "2_2") (pintype "passive"))
    )
    (net (code "68") (name "Net-(IC14A-PR0)") (class "Default")
      (node (ref "IC14") (pin "25") (pinfunction "PR0_25") (pintype "input"))
      (node (ref "R71") (pin "2") (pinfunction "2_2") (pintype "passive"))
    )
    (net (code "69") (name "Net-(IC14A-PR1)") (class "Default")
      (node (ref "IC14") (pin "26") (pinfunction "PR1_26") (pintype "input"))
      (node (ref "R72") (pin "2") (pinfunction "2_2") (pintype "passive"))
    )
    (net (code "70") (name "Net-(IC14A-REG_CAP1)") (class "Default")
      (node (ref "C158") (pin "1") (pinfunction "1_1") (pintype "passive"))
      (node (ref "IC14") (pin "19") (pinfunction "REG_CAP1_19") (pintype "passive"))
    )
    (net (code "71") (name "Net-(IC14A-REG_CAP2)") (class "Default")
      (node (ref "C157") (pin "1") (pinfunction "1_1") (pintype "passive"))
      (node (ref "IC14") (pin "17") (pinfunction "REG_CAP2_17") (pintype "passive"))
    )
    (net (code "72") (name "Net-(IC14B-VCC_IN)") (class "Default")
      (node (ref "C145") (pin "1") (pinfunction "1_1") (pintype "passive"))
      (node (ref "C147") (pin "2") (pinfunction "2_2") (pintype "passive"))
      (node (ref "C149") (pin "2") (pinfunction "2_2") (pintype "passive"))
      (node (ref "C150") (pin "2") (pinfunction "2_2") (pintype "passive"))
      (node (ref "IC14") (pin "16") (pinfunction "VCC_PLL2_16") (pintype "power_in"))
      (node (ref "IC14") (pin "18") (pinfunction "VCC_PLL1_18") (pintype "power_in"))
      (node (ref "IC14") (pin "20") (pinfunction "VCC_IN_20") (pintype "power_in"))
      (node (ref "IC14") (pin "9") (pinfunction "VCC_VCO_9") (pintype "power_in"))
      (node (ref "L7") (pin "1") (pinfunction "1_1") (pintype "passive"))
    )
    (net (code "73") (name "Net-(IC15A-D)") (class "Default")
      (node (ref "IC15") (pin "2") (pinfunction "D_2") (pintype "input"))
      (node (ref "IC16") (pin "28") (pinfunction "OUT5_28") (pintype "output"))
      (node (ref "IC49") (pin "2") (pinfunction "IN+_2") (pintype "input"))
      (node (ref "R78") (pin "1") (pinfunction "1_1") (pintype "passive"))
    )
    (net (code "74") (name "Net-(IC15A-Q)") (class "Default")
      (node (ref "IC15") (pin "7") (pinfunction "Q_7") (pintype "output"))
      (node (ref "R77") (pin "1") (pinfunction "1_1") (pintype "passive"))
    )
    (net (code "75") (name "Net-(IC15A-{slash}D)") (class "Default")
      (node (ref "IC15") (pin "3") (pinfunction "/D_3") (pintype "input"))
      (node (ref "IC16") (pin "29") (pinfunction "~{OUT5}_29") (pintype "output"))
      (node (ref "IC49") (pin "3") (pinfunction "IN-_3") (pintype "input"))
      (node (ref "R76") (pin "1") (pinfunction "1_1") (pintype "passive"))
    )
    (net (code "76") (name "Net-(IC16A-BYPASS)") (class "Default")
      (node (ref "C164") (pin "1") (pinfunction "1_1") (pintype "passive"))
      (node (ref "C165") (pin "1") (pinfunction "1_1") (pintype "passive"))
      (node (ref "C170") (pin "1") (pinfunction "1_1") (pintype "passive"))
      (node (ref "IC16") (pin "10") (pinfunction "BYPASS_10") (pintype "output"))
      (node (ref "R79") (pin "1") (pinfunction "1_1") (pintype "passive"))
    )
    (net (code "77") (name "Net-(IC16A-CLK)") (class "Default")
      (node (ref "C182") (pin "2") (pinfunction "2_2") (pintype "passive"))
      (node (ref "IC16") (pin "13") (pinfunction "CLK_13") (pintype "input"))
      (node (ref "R90") (pin "2") (pinfunction "2_2") (pintype "passive"))
    )
    (net (code "78") (name "Net-(IC16A-CP)") (class "Default")
      (node (ref "C168") (pin "2") (pinfunction "2_2") (pintype "passive"))
      (node (ref "C170") (pin "2") (pinfunction "2_2") (pintype "passive"))
      (node (ref "IC16") (pin "5") (pinfunction "CP_5") (pintype "output"))
      (node (ref "R80") (pin "2") (pinfunction "2_2") (pintype "passive"))
    )
    (net (code "79") (name "Net-(IC16A-CPRSET)") (class "Default")
      (node (ref "IC16") (pin "62") (pinfunction "CPRSET_62") (pintype "passive"))
      (node (ref "R86") (pin "2") (pinfunction "2_2") (pintype "passive"))
    )
    (net (code "80") (name "Net-(IC16A-LD)") (class "Default")
      (node (ref "IC16") (pin "3") (pinfunction "LD_3") (pintype "output"))
      (node (ref "R220") (pin "1") (pinfunction "1_1") (pintype "passive"))
    )
    (net (code "81") (name "Net-(IC16A-LF)") (class "Default")
      (node (ref "C164") (pin "2") (pinfunction "2_2") (pintype "passive"))
      (node (ref "IC16") (pin "9") (pinfunction "LF_9") (pintype "input"))
      (node (ref "R80") (pin "1") (pinfunction "1_1") (pintype "passive"))
    )
    (net (code "82") (name "Net-(IC16A-OUT0)") (class "Default")
      (node (ref "C90") (pin "2") (pinfunction "2_2") (pintype "passive"))
      (node (ref "IC16") (pin "56") (pinfunction "OUT0_56") (pintype "output"))
      (node (ref "R93") (pin "1") (pinfunction "1_1") (pintype "passive"))
    )
    (net (code "83") (name "Net-(IC16A-OUT1)") (class "Default")
      (node (ref "C101") (pin "2") (pinfunction "2_2") (pintype "passive"))
      (node (ref "IC16") (pin "53") (pinfunction "OUT1_53") (pintype "output"))
      (node (ref "R91") (pin "1") (pinfunction "1_1") (pintype "passive"))
    )
    (net (code "84") (name "Net-(IC16A-OUT2)") (class "Default")
      (node (ref "C103") (pin "2") (pinfunction "2_2") (pintype "passive"))
      (node (ref "IC16") (pin "43") (pinfunction "OUT2_43") (pintype "output"))
      (node (ref "R87") (pin "1") (pinfunction "1_1") (pintype "passive"))
    )
    (net (code "85") (name "Net-(IC16A-OUT3)") (class "Default")
      (node (ref "C125") (pin "2") (pinfunction "2_2") (pintype "passive"))
      (node (ref "IC16") (pin "40") (pinfunction "OUT3_40") (pintype "output"))
      (node (ref "R84") (pin "1") (pinfunction "1_1") (pintype "passive"))
    )
    (net (code "86") (name "Net-(IC16A-OUT4)") (class "Default")
      (node (ref "C139") (pin "2") (pinfunction "2_2") (pintype "passive"))
      (node (ref "IC16") (pin "25") (pinfunction "OUT4_25") (pintype "output"))
      (node (ref "R81") (pin "1") (pinfunction "1_1") (pintype "passive"))
    )
    (net (code "87") (name "Net-(IC16A-OUT9_(OUT9A))") (class "Default")
      (node (ref "IC16") (pin "35") (pinfunction "OUT9_(OUT9A)_35") (pintype "output"))
      (node (ref "R75") (pin "1") (pinfunction "1_1") (pintype "passive"))
    )
    (net (code "88") (name "Net-(IC16A-REFIN_(REF1))") (class "Default")
      (node (ref "C185") (pin "2") (pinfunction "2_2") (pintype "passive"))
      (node (ref "IC16") (pin "64") (pinfunction "REFIN_(REF1)_64") (pintype "input"))
    )
    (net (code "89") (name "Net-(IC16A-RSET)") (class "Default")
      (node (ref "IC16") (pin "58") (pinfunction "RSET_58") (pintype "passive"))
      (node (ref "R83") (pin "2") (pinfunction "2_2") (pintype "passive"))
    )
    (net (code "90") (name "Net-(IC16A-SDIO)") (class "Default")
      (node (ref "IC16") (pin "22") (pinfunction "SDIO_22") (pintype "bidirectional"))
      (node (ref "R224") (pin "1") (pinfunction "1_1") (pintype "passive"))
    )
    (net (code "91") (name "Net-(IC16A-SDO)") (class "Default")
      (node (ref "IC16") (pin "21") (pinfunction "SDO_21") (pintype "output"))
      (node (ref "R223") (pin "1") (pinfunction "1_1") (pintype "passive"))
    )
    (net (code "92") (name "Net-(IC16A-STATUS)") (class "Default")
      (node (ref "IC16") (pin "6") (pinfunction "STATUS_6") (pintype "output"))
      (node (ref "R225") (pin "1") (pinfunction "1_1") (pintype "passive"))
    )
    (net (code "93") (name "Net-(IC16A-~{CLK})") (class "Default")
      (node (ref "C179") (pin "2") (pinfunction "2_2") (pintype "passive"))
      (node (ref "IC16") (pin "14") (pinfunction "~{CLK}_14") (pintype "input"))
      (node (ref "R90") (pin "1") (pinfunction "1_1") (pintype "passive"))
    )
    (net (code "94") (name "Net-(IC16A-~{OUT0})") (class "Default")
      (node (ref "C89") (pin "2") (pinfunction "2_2") (pintype "passive"))
      (node (ref "IC16") (pin "55") (pinfunction "~{OUT0}_55") (pintype "output"))
      (node (ref "R92") (pin "1") (pinfunction "1_1") (pintype "passive"))
    )
    (net (code "95") (name "Net-(IC16A-~{OUT1})") (class "Default")
      (node (ref "C99") (pin "2") (pinfunction "2_2") (pintype "passive"))
      (node (ref "IC16") (pin "52") (pinfunction "~{OUT1}_52") (pintype "output"))
      (node (ref "R89") (pin "1") (pinfunction "1_1") (pintype "passive"))
    )
    (net (code "96") (name "Net-(IC16A-~{OUT2})") (class "Default")
      (node (ref "C102") (pin "2") (pinfunction "2_2") (pintype "passive"))
      (node (ref "IC16") (pin "42") (pinfunction "~{OUT2}_42") (pintype "output"))
      (node (ref "R88") (pin "1") (pinfunction "1_1") (pintype "passive"))
    )
    (net (code "97") (name "Net-(IC16A-~{OUT3})") (class "Default")
      (node (ref "C122") (pin "2") (pinfunction "2_2") (pintype "passive"))
      (node (ref "IC16") (pin "39") (pinfunction "~{OUT3}_39") (pintype "output"))
      (node (ref "R85") (pin "1") (pinfunction "1_1") (pintype "passive"))
    )
    (net (code "98") (name "Net-(IC16A-~{OUT4})") (class "Default")
      (node (ref "C138") (pin "2") (pinfunction "2_2") (pintype "passive"))
      (node (ref "IC16") (pin "26") (pinfunction "~{OUT4}_26") (pintype "output"))
      (node (ref "R82") (pin "1") (pinfunction "1_1") (pintype "passive"))
    )
    (net (code "99") (name "Net-(IC16A-~{OUT9}_(OUT9B))") (class "Default")
      (node (ref "IC16") (pin "36") (pinfunction "~{OUT9}_(OUT9B)_36") (pintype "output"))
      (node (ref "R74") (pin "1") (pinfunction "1_1") (pintype "passive"))
    )
    (net (code "100") (name "Net-(IC16A-~{REFIN}_(REF2))") (class "Default")
      (node (ref "C188") (pin "2") (pinfunction "2_2") (pintype "passive"))
      (node (ref "IC16") (pin "63") (pinfunction "~{REFIN}_(REF2)_63") (pintype "input"))
    )
    (net (code "101") (name "Net-(IC16B-VCP)") (class "Default")
      (node (ref "C160") (pin "1") (pinfunction "1_1") (pintype "passive"))
      (node (ref "C161") (pin "2") (pinfunction "2_2") (pintype "passive"))
      (node (ref "C163") (pin "2") (pinfunction "2_2") (pintype "passive"))
      (node (ref "IC16") (pin "4") (pinfunction "VCP_4") (pintype "power_in"))
      (node (ref "L8") (pin "1") (pinfunction "1_1") (pintype "passive"))
    )
    (net (code "102") (name "unconnected-(IC13A-OSC_OUT-Pad23)") (class "Default")
      (node (ref "IC13") (pin "23") (pinfunction "OSC_OUT_23") (pintype "output"))
    )
    (net (code "103") (name "unconnected-(IC14A-OSC_OUT-Pad23)") (class "Default")
      (node (ref "IC14") (pin "23") (pinfunction "OSC_OUT_23") (pintype "output"))
    )
    (net (code "104") (name "unconnected-(IC14A-OUTN1-Pad2)") (class "Default")
      (node (ref "IC14") (pin "2") (pinfunction "OUTN1_2") (pintype "output"))
    )
    (net (code "105") (name "unconnected-(IC14A-OUTP1-Pad3)") (class "Default")
      (node (ref "IC14") (pin "3") (pinfunction "OUTP1_3") (pintype "output"))
    )
    (net (code "106") (name "unconnected-(IC15A-VBB-Pad4)") (class "Default")
      (node (ref "IC15") (pin "4") (pinfunction "VBB_4") (pintype "passive"))
    )
    (net (code "107") (name "unconnected-(IC16A-OUT6_(OUT6A)-Pad48)") (class "Default")
      (node (ref "IC16") (pin "48") (pinfunction "OUT6_(OUT6A)_48") (pintype "output"))
    )
    (net (code "108") (name "unconnected-(IC16A-REFMON-Pad2)") (class "Default")
      (node (ref "IC16") (pin "2") (pinfunction "REFMON_2") (pintype "output"))
    )
    (net (code "109") (name "unconnected-(IC16A-~{OUT6}_(OUT6B)-Pad47)") (class "Default")
      (node (ref "IC16") (pin "47") (pinfunction "~{OUT6}_(OUT6B)_47") (pintype "output"))
    )
    (net (code "110") (name "unconnected-(IC49-NC-Pad1)") (class "Default")
      (node (ref "IC49") (pin "1") (pinfunction "NC_1") (pintype "passive+no_connect"))
    )
    (net (code "111") (name "unconnected-(IC49-NC-Pad4)") (class "Default")
      (node (ref "IC49") (pin "4") (pinfunction "NC_4") (pintype "passive+no_connect"))
    )
    (net (code "112") (name "unconnected-(IC49-NC-Pad5)") (class "Default")
      (node (ref "IC49") (pin "5") (pinfunction "NC_5") (pintype "passive+no_connect"))
    )
  )
)
